# power.net
KiCad netlist of a schematic drawn in Altium Designer
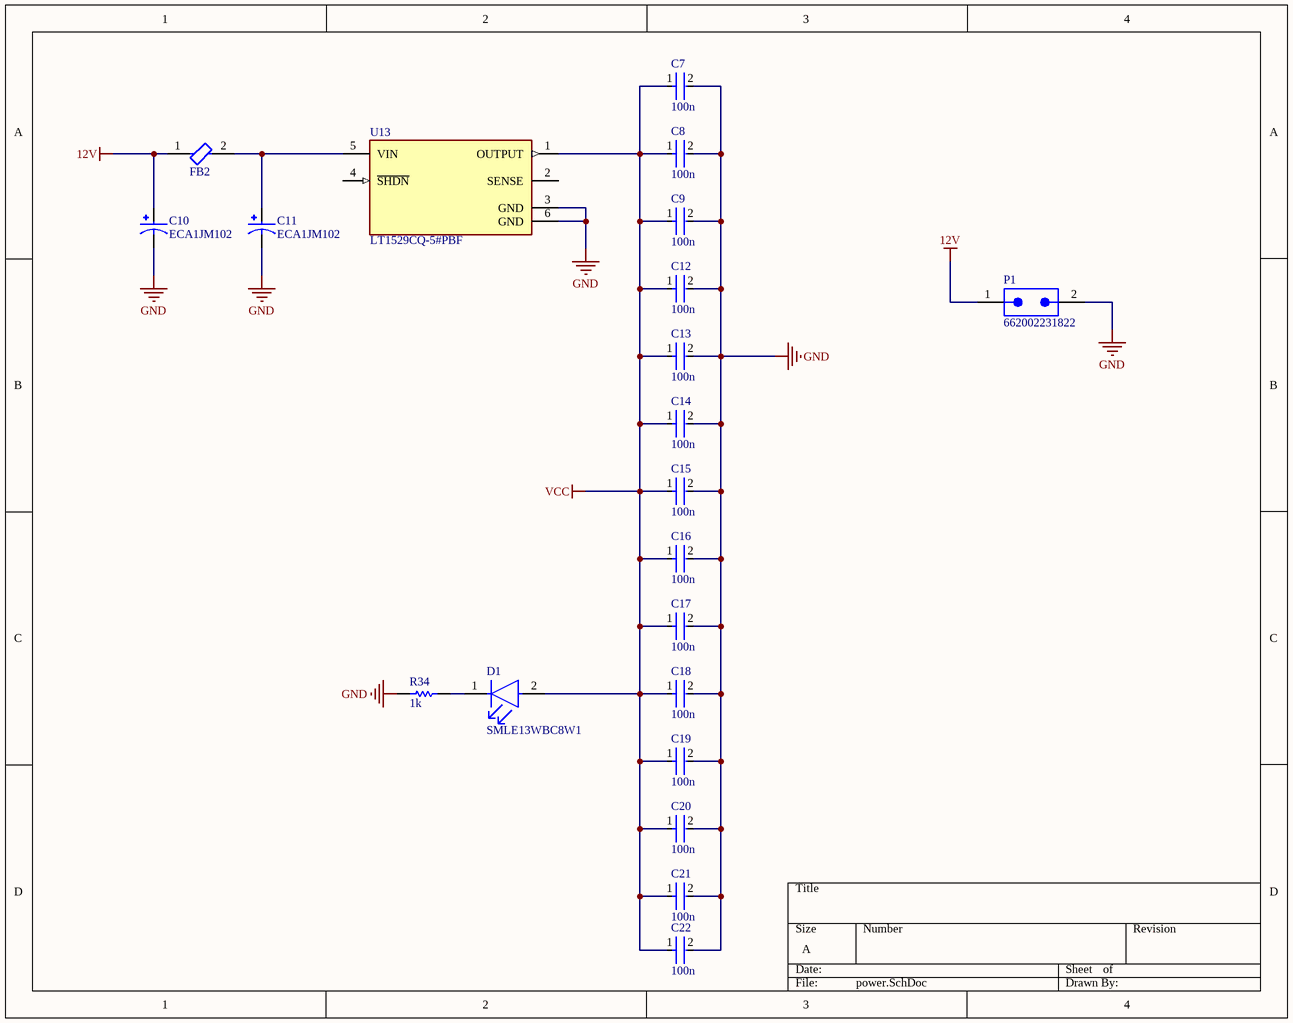
[diagram p0: power.SchDoc]

(export (version "E")
  (design (tool "Eeschema 10.0.6"))
  (components
    (comp (ref "C7")
      (value "100n")
      (footprint "FP-CL10-IPC_C")
      (description "Cap Ceramic 4.7uF 10V X5R ±10% Pad SMD 0603 +85°C T/R")
      (fields (field (name "TOLERANCE") "10%"))
      (libsource (lib "Altium Content Vault") (part "b4654b650e69147ec39a6b967a45e02"))
    )
    (comp (ref "C8")
      (value "100n")
      (footprint "FP-CL10-IPC_C")
      (description "Cap Ceramic 4.7uF 10V X5R ±10% Pad SMD 0603 +85°C T/R")
      (fields (field (name "TOLERANCE") "10%"))
      (libsource (lib "Altium Content Vault") (part "b4654b650e69147ec39a6b967a45e02"))
    )
    (comp (ref "C9")
      (value "100n")
      (footprint "FP-CL10-IPC_C")
      (description "Cap Ceramic 4.7uF 10V X5R ±10% Pad SMD 0603 +85°C T/R")
      (fields (field (name "TOLERANCE") "10%"))
      (libsource (lib "Altium Content Vault") (part "b4654b650e69147ec39a6b967a45e02"))
    )
    (comp (ref "C10")
      (value "ECA1JM102")
      (footprint "CAPPRD750W80D1600H2500")
      (description "1000ÂµF 63V Aluminum Electrolytic Capacitors Radial, Can 2000 Hrs @ 85Â°C")
      (fields (field (name "MF") "Panasonic"))
      (libsource (lib "ECA1JM102") (part "ECA1JM102"))
    )
    (comp (ref "C11")
      (value "ECA1JM102")
      (footprint "CAPPRD750W80D1600H2500")
      (description "1000ÂµF 63V Aluminum Electrolytic Capacitors Radial, Can 2000 Hrs @ 85Â°C")
      (fields (field (name "MF") "Panasonic"))
      (libsource (lib "ECA1JM102") (part "ECA1JM102"))
    )
    (comp (ref "C12")
      (value "100n")
      (footprint "FP-CL10-IPC_C")
      (description "Cap Ceramic 4.7uF 10V X5R ±10% Pad SMD 0603 +85°C T/R")
      (fields (field (name "TOLERANCE") "10%"))
      (libsource (lib "Altium Content Vault") (part "b4654b650e69147ec39a6b967a45e02"))
    )
    (comp (ref "C13")
      (value "100n")
      (footprint "FP-CL10-IPC_C")
      (description "Cap Ceramic 4.7uF 10V X5R ±10% Pad SMD 0603 +85°C T/R")
      (fields (field (name "TOLERANCE") "10%"))
      (libsource (lib "Altium Content Vault") (part "b4654b650e69147ec39a6b967a45e02"))
    )
    (comp (ref "C14")
      (value "100n")
      (footprint "FP-CL10-IPC_C")
      (description "Cap Ceramic 4.7uF 10V X5R ±10% Pad SMD 0603 +85°C T/R")
      (fields (field (name "TOLERANCE") "10%"))
      (libsource (lib "Altium Content Vault") (part "b4654b650e69147ec39a6b967a45e02"))
    )
    (comp (ref "C15")
      (value "100n")
      (footprint "FP-CL10-IPC_C")
      (description "Cap Ceramic 4.7uF 10V X5R ±10% Pad SMD 0603 +85°C T/R")
      (fields (field (name "TOLERANCE") "10%"))
      (libsource (lib "Altium Content Vault") (part "b4654b650e69147ec39a6b967a45e02"))
    )
    (comp (ref "C16")
      (value "100n")
      (footprint "FP-CL10-IPC_C")
      (description "Cap Ceramic 4.7uF 10V X5R ±10% Pad SMD 0603 +85°C T/R")
      (fields (field (name "TOLERANCE") "10%"))
      (libsource (lib "Altium Content Vault") (part "b4654b650e69147ec39a6b967a45e02"))
    )
    (comp (ref "C17")
      (value "100n")
      (footprint "FP-CL10-IPC_C")
      (description "Cap Ceramic 4.7uF 10V X5R ±10% Pad SMD 0603 +85°C T/R")
      (fields (field (name "TOLERANCE") "10%"))
      (libsource (lib "Altium Content Vault") (part "b4654b650e69147ec39a6b967a45e02"))
    )
    (comp (ref "C18")
      (value "100n")
      (footprint "FP-CL10-IPC_C")
      (description "Cap Ceramic 4.7uF 10V X5R ±10% Pad SMD 0603 +85°C T/R")
      (fields (field (name "TOLERANCE") "10%"))
      (libsource (lib "Altium Content Vault") (part "b4654b650e69147ec39a6b967a45e02"))
    )
    (comp (ref "C19")
      (value "100n")
      (footprint "FP-CL10-IPC_C")
      (description "Cap Ceramic 4.7uF 10V X5R ±10% Pad SMD 0603 +85°C T/R")
      (fields (field (name "TOLERANCE") "10%"))
      (libsource (lib "Altium Content Vault") (part "b4654b650e69147ec39a6b967a45e02"))
    )
    (comp (ref "C20")
      (value "100n")
      (footprint "FP-CL10-IPC_C")
      (description "Cap Ceramic 4.7uF 10V X5R ±10% Pad SMD 0603 +85°C T/R")
      (fields (field (name "TOLERANCE") "10%"))
      (libsource (lib "Altium Content Vault") (part "b4654b650e69147ec39a6b967a45e02"))
    )
    (comp (ref "C21")
      (value "100n")
      (footprint "FP-CL10-IPC_C")
      (description "Cap Ceramic 4.7uF 10V X5R ±10% Pad SMD 0603 +85°C T/R")
      (fields (field (name "TOLERANCE") "10%"))
      (libsource (lib "Altium Content Vault") (part "b4654b650e69147ec39a6b967a45e02"))
    )
    (comp (ref "C22")
      (value "100n")
      (footprint "FP-CL10-IPC_C")
      (description "Cap Ceramic 4.7uF 10V X5R ±10% Pad SMD 0603 +85°C T/R")
      (fields (field (name "TOLERANCE") "10%"))
      (libsource (lib "Altium Content Vault") (part "b4654b650e69147ec39a6b967a45e02"))
    )
    (comp (ref "D1")
      (value "SMLE13WBC8W1")
      (footprint "FP-SMLE13WBC8W1-MFG")
      (description "LED WHITE 0603 SMD")
      (fields
        (field (name "OCTOPART") "https://octopart.com/smle13wbc8w1-rohm-22224565")
        (field (name "MANUFACTURER") "Rohm")
      )
      (libsource (lib "Altium Content Vault") (part "8706943c75ba83719d021d2fdc84c58"))
    )
    (comp (ref "FB2")
      (value "BLM18KG121TN1D")
      (footprint "FP-BLM18-0_15-t0_6-d1_2-IPC_A")
      (description "FERRITE BEAD 120 OHM 0603 1LN")
      (fields (field (name "TOLERANCE") "25%"))
      (libsource (lib "Altium Content Vault") (part "5f30dd21d616792df468990f7003faa"))
    )
    (comp (ref "P1")
      (value "662002231822")
      (footprint "662002231822")
      (libsource (lib "Altium Content Vault") (part "Header_Male_2R_02P(A)"))
    )
    (comp (ref "R34")
      (value "1k")
      (footprint "RESC2013X60X35ML10T20")
      (fields (field (name "TOLERANCE") "5%") (field (name "MANUFACTURER") "Yageo"))
      (libsource (lib "Altium Content Vault") (part "RES-2"))
    )
    (comp (ref "U13")
      (value "LT1529CQ-5#PBF")
      (footprint "FP-Q-5-05-08-1461-MFG")
      (libsource (lib "Altium Content Vault") (part "44439a2b2ec2a3ca22c25b3ab113aa0"))
    )
  )
  (nets
    (net (code "1") (name "12V") (class "Default")
      (node (ref "C10") (pin "P") (pinfunction "P_P") (pintype "passive"))
      (node (ref "FB2") (pin "1") (pinfunction "1_1") (pintype "passive"))
      (node (ref "P1") (pin "1") (pinfunction "1_1") (pintype "passive"))
    )
    (net (code "2") (name "GND") (class "Default")
      (node (ref "C10") (pin "N") (pinfunction "N_N") (pintype "passive"))
      (node (ref "C11") (pin "N") (pinfunction "N_N") (pintype "passive"))
      (node (ref "C12") (pin "2") (pinfunction "2_2") (pintype "passive"))
      (node (ref "C13") (pin "2") (pinfunction "2_2") (pintype "passive"))
      (node (ref "C14") (pin "2") (pinfunction "2_2") (pintype "passive"))
      (node (ref "C15") (pin "2") (pinfunction "2_2") (pintype "passive"))
      (node (ref "C16") (pin "2") (pinfunction "2_2") (pintype "passive"))
      (node (ref "C17") (pin "2") (pinfunction "2_2") (pintype "passive"))
      (node (ref "C18") (pin "2") (pinfunction "2_2") (pintype "passive"))
      (node (ref "C19") (pin "2") (pinfunction "2_2") (pintype "passive"))
      (node (ref "C20") (pin "2") (pinfunction "2_2") (pintype "passive"))
      (node (ref "C21") (pin "2") (pinfunction "2_2") (pintype "passive"))
      (node (ref "C22") (pin "2") (pinfunction "2_2") (pintype "passive"))
      (node (ref "C7") (pin "2") (pinfunction "2_2") (pintype "passive"))
      (node (ref "C8") (pin "2") (pinfunction "2_2") (pintype "passive"))
      (node (ref "C9") (pin "2") (pinfunction "2_2") (pintype "passive"))
      (node (ref "P1") (pin "2") (pinfunction "2_2") (pintype "passive"))
      (node (ref "R34") (pin "1") (pinfunction "1_1") (pintype "passive"))
      (node (ref "U13") (pin "3") (pinfunction "GND_3") (pintype "power_in"))
      (node (ref "U13") (pin "6") (pinfunction "GND_6") (pintype "power_in"))
    )
    (net (code "3") (name "Net-(D1-C)") (class "Default")
      (node (ref "D1") (pin "1") (pinfunction "C_1") (pintype "passive"))
      (node (ref "R34") (pin "2") (pinfunction "2_2") (pintype "passive"))
    )
    (net (code "4") (name "Net-(U13-VIN)") (class "Default")
      (node (ref "C11") (pin "P") (pinfunction "P_P") (pintype "passive"))
      (node (ref "FB2") (pin "2") (pinfunction "2_2") (pintype "passive"))
      (node (ref "U13") (pin "5") (pinfunction "VIN_5") (pintype "power_in"))
    )
    (net (code "5") (name "VCC") (class "Default")
      (node (ref "C12") (pin "1") (pinfunction "1_1") (pintype "passive"))
      (node (ref "C13") (pin "1") (pinfunction "1_1") (pintype "passive"))
      (node (ref "C14") (pin "1") (pinfunction "1_1") (pintype "passive"))
      (node (ref "C15") (pin "1") (pinfunction "1_1") (pintype "passive"))
      (node (ref "C16") (pin "1") (pinfunction "1_1") (pintype "passive"))
      (node (ref "C17") (pin "1") (pinfunction "1_1") (pintype "passive"))
      (node (ref "C18") (pin "1") (pinfunction "1_1") (pintype "passive"))
      (node (ref "C19") (pin "1") (pinfunction "1_1") (pintype "passive"))
      (node (ref "C20") (pin "1") (pinfunction "1_1") (pintype "passive"))
      (node (ref "C21") (pin "1") (pinfunction "1_1") (pintype "passive"))
      (node (ref "C22") (pin "1") (pinfunction "1_1") (pintype "passive"))
      (node (ref "C7") (pin "1") (pinfunction "1_1") (pintype "passive"))
      (node (ref "C8") (pin "1") (pinfunction "1_1") (pintype "passive"))
      (node (ref "C9") (pin "1") (pinfunction "1_1") (pintype "passive"))
      (node (ref "D1") (pin "2") (pinfunction "A_2") (pintype "passive"))
      (node (ref "U13") (pin "1") (pinfunction "OUTPUT_1") (pintype "output"))
    )
    (net (code "6") (name "unconnected-(U13-SENSE-Pad2)") (class "Default")
      (node (ref "U13") (pin "2") (pinfunction "SENSE_2") (pintype "passive"))
    )
    (net (code "7") (name "unconnected-(U13-~{SHDN}-Pad4)") (class "Default")
      (node (ref "U13") (pin "4") (pinfunction "~{SHDN}_4") (pintype "input"))
    )
  )
)
